# Power.net
KiCad netlist of a schematic drawn in Altium Designer
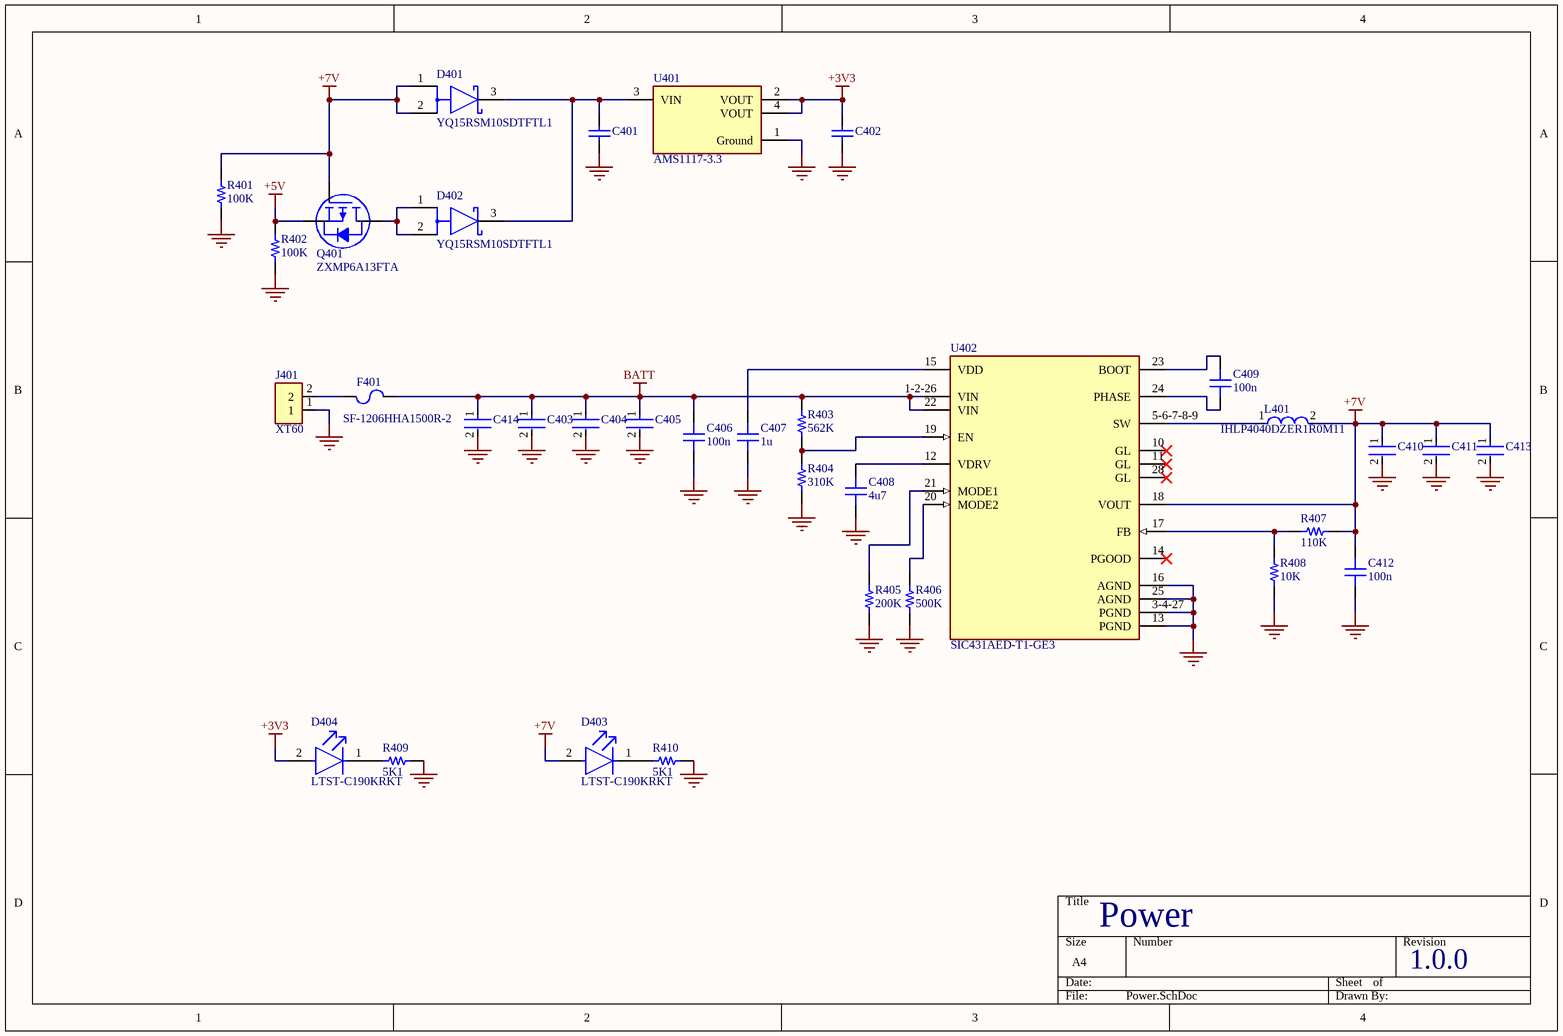
[diagram p0: Power.SchDoc]

(export (version "E")
  (design (tool "Eeschema 10.0.6"))
  (components
    (comp (ref "C401")
      (value "T529P226M010AAE200")
      (footprint "CAPC2013X100X55ML10T10")
      (fields (field (name "MANUFACTURER") "Kemet"))
      (libsource (lib "Altium Content Vault") (part "CAP"))
    )
    (comp (ref "C402")
      (value "T529P226M010AAE200")
      (footprint "CAPC2013X100X55ML10T10")
      (fields (field (name "MANUFACTURER") "Kemet"))
      (libsource (lib "Altium Content Vault") (part "CAP"))
    )
    (comp (ref "C403")
      (value "C2012X5R1V226M125AC")
      (footprint "FP-C2012-125-0_2-IPC_C")
      (description "Multilayer Ceramic Capacitors 22μF ±20% 35V X5R SMD 0805")
      (fields (field (name "TOLERANCE") "20%"))
      (libsource (lib "Altium Content Vault") (part "b4654b650e69147ec39a6b967a45e02"))
    )
    (comp (ref "C404")
      (value "C2012X5R1V226M125AC")
      (footprint "FP-C2012-125-0_2-IPC_C")
      (description "Multilayer Ceramic Capacitors 22μF ±20% 35V X5R SMD 0805")
      (fields (field (name "TOLERANCE") "20%"))
      (libsource (lib "Altium Content Vault") (part "b4654b650e69147ec39a6b967a45e02"))
    )
    (comp (ref "C405")
      (value "C2012X5R1V226M125AC")
      (footprint "FP-C2012-125-0_2-IPC_C")
      (description "Multilayer Ceramic Capacitors 22μF ±20% 35V X5R SMD 0805")
      (fields (field (name "TOLERANCE") "20%"))
      (libsource (lib "Altium Content Vault") (part "b4654b650e69147ec39a6b967a45e02"))
    )
    (comp (ref "C406")
      (value "100n")
      (footprint "CAP 0402_1005")
      (description "CAP CER 100NF 10V X7R 0402")
      (fields
        (field (name "PART NUMBER") "CL05B104KP5VPNC")
        (field (name "MANUFACTURER") "Samsung Electro-Mechanics")
      )
      (libsource (lib "Celestial Altium Library - altium_library") (part "Capacitor"))
    )
    (comp (ref "C407")
      (value "1u")
      (footprint "CAP 0402_1005")
      (description "CAP CER 100NF 10V X7R 0402")
      (fields
        (field (name "PART NUMBER") "CL05B104KP5VPNC")
        (field (name "MANUFACTURER") "Samsung Electro-Mechanics")
      )
      (libsource (lib "Celestial Altium Library - altium_library") (part "Capacitor"))
    )
    (comp (ref "C408")
      (value "4u7")
      (footprint "CAP 0603_1608")
      (description "CAP CER 4.7UF 25V X5R 0603")
      (fields
        (field (name "PART NUMBER") "CL10A475KA8NQNC")
        (field (name "MANUFACTURER") "Samsung Electro-Mechanics")
      )
      (libsource (lib "Celestial Altium Library - altium_library") (part "Capacitor"))
    )
    (comp (ref "C409")
      (value "100n")
      (footprint "CAP 0402_1005")
      (description "CAP CER 100NF 10V X7R 0402")
      (fields
        (field (name "PART NUMBER") "CL05B104KP5VPNC")
        (field (name "MANUFACTURER") "Samsung Electro-Mechanics")
      )
      (libsource (lib "Celestial Altium Library - altium_library") (part "Capacitor"))
    )
    (comp (ref "C410")
      (value "C2012X5R1V226M125AC")
      (footprint "FP-C2012-125-0_2-IPC_C")
      (description "Multilayer Ceramic Capacitors 22μF ±20% 35V X5R SMD 0805")
      (fields (field (name "TOLERANCE") "20%"))
      (libsource (lib "Altium Content Vault") (part "b4654b650e69147ec39a6b967a45e02"))
    )
    (comp (ref "C411")
      (value "C2012X5R1V226M125AC")
      (footprint "FP-C2012-125-0_2-IPC_C")
      (description "Multilayer Ceramic Capacitors 22μF ±20% 35V X5R SMD 0805")
      (fields (field (name "TOLERANCE") "20%"))
      (libsource (lib "Altium Content Vault") (part "b4654b650e69147ec39a6b967a45e02"))
    )
    (comp (ref "C412")
      (value "100n")
      (footprint "CAP 0402_1005")
      (description "CAP CER 100NF 10V X7R 0402")
      (fields
        (field (name "PART NUMBER") "CL05B104KP5VPNC")
        (field (name "MANUFACTURER") "Samsung Electro-Mechanics")
      )
      (libsource (lib "Celestial Altium Library - altium_library") (part "Capacitor"))
    )
    (comp (ref "C413")
      (value "C2012X5R1V226M125AC")
      (footprint "FP-C2012-125-0_2-IPC_C")
      (description "Multilayer Ceramic Capacitors 22μF ±20% 35V X5R SMD 0805")
      (fields (field (name "TOLERANCE") "20%"))
      (libsource (lib "Altium Content Vault") (part "b4654b650e69147ec39a6b967a45e02"))
    )
    (comp (ref "C414")
      (value "C2012X5R1V226M125AC")
      (footprint "FP-C2012-125-0_2-IPC_C")
      (description "Multilayer Ceramic Capacitors 22μF ±20% 35V X5R SMD 0805")
      (fields (field (name "TOLERANCE") "20%"))
      (libsource (lib "Altium Content Vault") (part "b4654b650e69147ec39a6b967a45e02"))
    )
    (comp (ref "D401")
      (value "YQ15RSM10SDTFTL1")
      (footprint "FP-95570-MFG")
      (description "DIODE SCHOTTKY 100V 5A TO277A")
      (libsource (lib "Altium Content Vault") (part "03725f8997c85b601c823eea96032f8"))
    )
    (comp (ref "D402")
      (value "YQ15RSM10SDTFTL1")
      (footprint "FP-95570-MFG")
      (description "DIODE SCHOTTKY 100V 5A TO277A")
      (libsource (lib "Altium Content Vault") (part "03725f8997c85b601c823eea96032f8"))
    )
    (comp (ref "D403")
      (value "LTST-C190KRKT")
      (footprint "FP-LTST-C190KRKT-MFG")
      (description "LED RED CLEAR CHIP SMD")
      (libsource (lib "Altium Content Vault") (part "8706943c75ba83719d021d2fdc84c58"))
    )
    (comp (ref "D404")
      (value "LTST-C190KRKT")
      (footprint "FP-LTST-C190KRKT-MFG")
      (description "LED RED CLEAR CHIP SMD")
      (libsource (lib "Altium Content Vault") (part "8706943c75ba83719d021d2fdc84c58"))
    )
    (comp (ref "F401")
      (value "SF-1206HHA1500R-2")
      (footprint "FUSE 1206_3216 0.6MM")
      (description "FUSE BOARD MOUNT 15A 32VDC 1206")
      (fields
        (field (name "PART NUMBER") "CC12H15A-TR")
        (field (name "MANUFACTURER") "Eaton - Electronics Division")
      )
      (libsource (lib "Celestial Altium Library - altium_library") (part "MOUNTED FUSE"))
    )
    (comp (ref "J401")
      (value "XT60")
      (footprint "AMASS_XT60PB-M")
      (description "Power connector; 65A; PIN: 2; Colour: yellow")
      (fields (field (name "MP") "XT60 YELLOW") (field (name "MF") "Pololu"))
      (libsource (lib "XT60_YELLOW") (part "XT60_YELLOW"))
    )
    (comp (ref "L401")
      (value "IHLP4040DZER1R0M11")
      (footprint "FP-IHLP-4040DZ-FP_3_175x4-MFG")
      (description "Commercial Inductors, Low DCR Series 1uH 25A 2.5mΩ 20%")
      (fields (field (name "TOLERANCE") "20%"))
      (libsource (lib "Altium Content Vault") (part "725321dda6339637d4d059423bc1c3c"))
    )
    (comp (ref "Q401")
      (value "ZXMP6A13FTA")
      (footprint "DIODES SOT-23-3")
      (description "MOSFET P-CH 60V 900MA SOT23-3")
      (fields (field (name "MANUFACTURER") "Diodes Incorporated"))
      (libsource (lib "Celestial Altium Library - altium_library") (part "DIODES MOSFET P-CH SOT-23-3"))
    )
    (comp (ref "R401")
      (value "100K")
      (footprint "RES 0402_1005")
      (description "RES SMD 5.1K OHM 5% 1/16W 0402")
      (fields (field (name "PART NUMBER") "AC0402JR-075K1L") (field (name "MANUFACTURER") "Yageo"))
      (libsource (lib "Celestial Altium Library - altium_library") (part "Resistor"))
    )
    (comp (ref "R402")
      (value "100K")
      (footprint "RES 0402_1005")
      (description "RES SMD 5.1K OHM 5% 1/16W 0402")
      (fields (field (name "PART NUMBER") "AC0402JR-075K1L") (field (name "MANUFACTURER") "Yageo"))
      (libsource (lib "Celestial Altium Library - altium_library") (part "Resistor"))
    )
    (comp (ref "R403")
      (value "562K")
      (footprint "RES 0402_1005")
      (description "RES SMD 5.1K OHM 5% 1/16W 0402")
      (fields (field (name "PART NUMBER") "AC0402JR-075K1L") (field (name "MANUFACTURER") "Yageo"))
      (libsource (lib "Celestial Altium Library - altium_library") (part "Resistor"))
    )
    (comp (ref "R404")
      (value "310K")
      (footprint "RES 0402_1005")
      (description "RES SMD 5.1K OHM 5% 1/16W 0402")
      (fields (field (name "PART NUMBER") "AC0402JR-075K1L") (field (name "MANUFACTURER") "Yageo"))
      (libsource (lib "Celestial Altium Library - altium_library") (part "Resistor"))
    )
    (comp (ref "R405")
      (value "200K")
      (footprint "RES 0402_1005")
      (description "RES SMD 5.1K OHM 5% 1/16W 0402")
      (fields (field (name "PART NUMBER") "AC0402JR-075K1L") (field (name "MANUFACTURER") "Yageo"))
      (libsource (lib "Celestial Altium Library - altium_library") (part "Resistor"))
    )
    (comp (ref "R406")
      (value "500K")
      (footprint "RES 0402_1005")
      (description "RES SMD 5.1K OHM 5% 1/16W 0402")
      (fields (field (name "PART NUMBER") "AC0402JR-075K1L") (field (name "MANUFACTURER") "Yageo"))
      (libsource (lib "Celestial Altium Library - altium_library") (part "Resistor"))
    )
    (comp (ref "R407")
      (value "110K")
      (footprint "RES 0402_1005")
      (description "RES SMD 5.1K OHM 5% 1/16W 0402")
      (fields (field (name "PART NUMBER") "AC0402JR-075K1L") (field (name "MANUFACTURER") "Yageo"))
      (libsource (lib "Celestial Altium Library - altium_library") (part "Resistor"))
    )
    (comp (ref "R408")
      (value "10K")
      (footprint "RES 0402_1005")
      (description "RES SMD 5.1K OHM 5% 1/16W 0402")
      (fields (field (name "PART NUMBER") "AC0402JR-075K1L") (field (name "MANUFACTURER") "Yageo"))
      (libsource (lib "Celestial Altium Library - altium_library") (part "Resistor"))
    )
    (comp (ref "R409")
      (value "5K1")
      (footprint "RES 0402_1005")
      (description "RES SMD 5.1K OHM 5% 1/16W 0402")
      (fields (field (name "PART NUMBER") "AC0402JR-075K1L") (field (name "MANUFACTURER") "Yageo"))
      (libsource (lib "Celestial Altium Library - altium_library") (part "Resistor"))
    )
    (comp (ref "R410")
      (value "5K1")
      (footprint "RES 0402_1005")
      (description "RES SMD 5.1K OHM 5% 1/16W 0402")
      (fields (field (name "PART NUMBER") "AC0402JR-075K1L") (field (name "MANUFACTURER") "Yageo"))
      (libsource (lib "Celestial Altium Library - altium_library") (part "Resistor"))
    )
    (comp (ref "U401")
      (value "AMS1117-3.3")
      (footprint "FP-AMS1117-IPC_C")
      (description "LDO Voltage Regulators 1A, 3.3V")
      (fields
        (field (name "OCTOPART") "https://octopart.com/ams1117-3.3-advanced+monolithic+systems-25899300")
        (field (name "MANUFACTURER") "Advanced Monolithic Systems")
      )
      (libsource (lib "Altium Content Vault") (part "8bdbb5f8e77002000e30dd2845d0354"))
    )
    (comp (ref "U402")
      (value "SIC431AED-T1-GE3")
      (footprint "FP-T22-0442-MFG")
      (description "SIC431AED-T1-GE3 IC Reg Buck Adj 24A MLP44-24")
      (libsource (lib "Altium Content Vault") (part "40dafd62ff4b33f9f37e65bbcadf93f"))
    )
  )
  (nets
    (net (code "1") (name "+3V3") (class "Default")
      (node (ref "C402") (pin "2") (pinfunction "2_2") (pintype "passive"))
      (node (ref "D404") (pin "2") (pinfunction "A_2") (pintype "passive"))
      (node (ref "U401") (pin "2") (pinfunction "VOUT_2") (pintype "passive"))
      (node (ref "U401") (pin "4") (pinfunction "VOUT_4") (pintype "passive"))
    )
    (net (code "2") (name "+5V") (class "Default")
      (node (ref "Q401") (pin "2") (pinfunction "S_2") (pintype "passive"))
      (node (ref "R402") (pin "2") (pinfunction "2_2") (pintype "passive"))
    )
    (net (code "3") (name "+7V") (class "Default")
      (node (ref "C410") (pin "1") (pinfunction "1_1") (pintype "passive"))
      (node (ref "C411") (pin "1") (pinfunction "1_1") (pintype "passive"))
      (node (ref "C412") (pin "2") (pinfunction "2_2") (pintype "passive"))
      (node (ref "C413") (pin "1") (pinfunction "1_1") (pintype "passive"))
      (node (ref "D401") (pin "1") (pinfunction "A_1") (pintype "passive"))
      (node (ref "D401") (pin "2") (pinfunction "A_2") (pintype "passive"))
      (node (ref "D403") (pin "2") (pinfunction "A_2") (pintype "passive"))
      (node (ref "L401") (pin "2") (pinfunction "2_2") (pintype "passive"))
      (node (ref "Q401") (pin "1") (pinfunction "G_1") (pintype "passive"))
      (node (ref "R401") (pin "2") (pinfunction "2_2") (pintype "passive"))
      (node (ref "R407") (pin "1") (pinfunction "1_1") (pintype "passive"))
      (node (ref "U402") (pin "18") (pinfunction "VOUT_18") (pintype "passive"))
    )
    (net (code "4") (name "BATT") (class "Default")
      (node (ref "C403") (pin "1") (pinfunction "1_1") (pintype "passive"))
      (node (ref "C404") (pin "1") (pinfunction "1_1") (pintype "passive"))
      (node (ref "C405") (pin "1") (pinfunction "1_1") (pintype "passive"))
      (node (ref "C406") (pin "2") (pinfunction "2_2") (pintype "passive"))
      (node (ref "C414") (pin "1") (pinfunction "1_1") (pintype "passive"))
      (node (ref "F401") (pin "2") (pintype "passive"))
      (node (ref "R403") (pin "1") (pinfunction "1_1") (pintype "passive"))
      (node (ref "U402") (pin "1-2-26") (pinfunction "VIN_1-2-26") (pintype "power_in"))
      (node (ref "U402") (pin "22") (pinfunction "VIN_22") (pintype "power_in"))
    )
    (net (code "5") (name "GND") (class "Default")
      (node (ref "C401") (pin "1") (pinfunction "1_1") (pintype "passive"))
      (node (ref "C402") (pin "1") (pinfunction "1_1") (pintype "passive"))
      (node (ref "C403") (pin "2") (pinfunction "2_2") (pintype "passive"))
      (node (ref "C404") (pin "2") (pinfunction "2_2") (pintype "passive"))
      (node (ref "C405") (pin "2") (pinfunction "2_2") (pintype "passive"))
      (node (ref "C406") (pin "1") (pinfunction "1_1") (pintype "passive"))
      (node (ref "C407") (pin "1") (pinfunction "1_1") (pintype "passive"))
      (node (ref "C408") (pin "1") (pinfunction "1_1") (pintype "passive"))
      (node (ref "C410") (pin "2") (pinfunction "2_2") (pintype "passive"))
      (node (ref "C411") (pin "2") (pinfunction "2_2") (pintype "passive"))
      (node (ref "C412") (pin "1") (pinfunction "1_1") (pintype "passive"))
      (node (ref "C413") (pin "2") (pinfunction "2_2") (pintype "passive"))
      (node (ref "C414") (pin "2") (pinfunction "2_2") (pintype "passive"))
      (node (ref "J401") (pin "1") (pinfunction "1_1") (pintype "passive"))
      (node (ref "R401") (pin "1") (pinfunction "1_1") (pintype "passive"))
      (node (ref "R402") (pin "1") (pinfunction "1_1") (pintype "passive"))
      (node (ref "R404") (pin "2") (pinfunction "2_2") (pintype "passive"))
      (node (ref "R405") (pin "2") (pinfunction "2_2") (pintype "passive"))
      (node (ref "R406") (pin "2") (pinfunction "2_2") (pintype "passive"))
      (node (ref "R408") (pin "2") (pinfunction "2_2") (pintype "passive"))
      (node (ref "R409") (pin "1") (pinfunction "1_1") (pintype "passive"))
      (node (ref "R410") (pin "1") (pinfunction "1_1") (pintype "passive"))
      (node (ref "U401") (pin "1") (pinfunction "Ground_1") (pintype "power_in"))
      (node (ref "U402") (pin "13") (pinfunction "PGND_13") (pintype "power_in"))
      (node (ref "U402") (pin "16") (pinfunction "AGND_16") (pintype "power_in"))
      (node (ref "U402") (pin "25") (pinfunction "AGND_25") (pintype "power_in"))
      (node (ref "U402") (pin "3-4-27") (pinfunction "PGND_3-4-27") (pintype "power_in"))
    )
    (net (code "6") (name "Net-(D401-C)") (class "Default")
      (node (ref "C401") (pin "2") (pinfunction "2_2") (pintype "passive"))
      (node (ref "D401") (pin "3") (pinfunction "C_3") (pintype "passive"))
      (node (ref "D402") (pin "3") (pinfunction "C_3") (pintype "passive"))
      (node (ref "U401") (pin "3") (pinfunction "VIN_3") (pintype "power_in"))
    )
    (net (code "7") (name "Net-(D403-C)") (class "Default")
      (node (ref "D403") (pin "1") (pinfunction "C_1") (pintype "passive"))
      (node (ref "R410") (pin "2") (pinfunction "2_2") (pintype "passive"))
    )
    (net (code "8") (name "Net-(D404-C)") (class "Default")
      (node (ref "D404") (pin "1") (pinfunction "C_1") (pintype "passive"))
      (node (ref "R409") (pin "2") (pinfunction "2_2") (pintype "passive"))
    )
    (net (code "9") (name "Net-(F401-Pad1)") (class "Default")
      (node (ref "F401") (pin "1") (pintype "passive"))
      (node (ref "J401") (pin "2") (pinfunction "2_2") (pintype "passive"))
    )
    (net (code "10") (name "Net-(Q401-D)") (class "Default")
      (node (ref "D402") (pin "1") (pinfunction "A_1") (pintype "passive"))
      (node (ref "D402") (pin "2") (pinfunction "A_2") (pintype "passive"))
      (node (ref "Q401") (pin "3") (pinfunction "D_3") (pintype "passive"))
    )
    (net (code "11") (name "Net-(U402-BOOT)") (class "Default")
      (node (ref "C409") (pin "2") (pinfunction "2_2") (pintype "passive"))
      (node (ref "U402") (pin "23") (pinfunction "BOOT_23") (pintype "passive"))
    )
    (net (code "12") (name "Net-(U402-EN)") (class "Default")
      (node (ref "R403") (pin "2") (pinfunction "2_2") (pintype "passive"))
      (node (ref "R404") (pin "1") (pinfunction "1_1") (pintype "passive"))
      (node (ref "U402") (pin "19") (pinfunction "EN_19") (pintype "input"))
    )
    (net (code "13") (name "Net-(U402-FB)") (class "Default")
      (node (ref "R407") (pin "2") (pinfunction "2_2") (pintype "passive"))
      (node (ref "R408") (pin "1") (pinfunction "1_1") (pintype "passive"))
      (node (ref "U402") (pin "17") (pinfunction "FB_17") (pintype "input"))
    )
    (net (code "14") (name "Net-(U402-MODE1)") (class "Default")
      (node (ref "R405") (pin "1") (pinfunction "1_1") (pintype "passive"))
      (node (ref "U402") (pin "21") (pinfunction "MODE1_21") (pintype "input"))
    )
    (net (code "15") (name "Net-(U402-MODE2)") (class "Default")
      (node (ref "R406") (pin "1") (pinfunction "1_1") (pintype "passive"))
      (node (ref "U402") (pin "20") (pinfunction "MODE2_20") (pintype "input"))
    )
    (net (code "16") (name "Net-(U402-PHASE)") (class "Default")
      (node (ref "C409") (pin "1") (pinfunction "1_1") (pintype "passive"))
      (node (ref "U402") (pin "24") (pinfunction "PHASE_24") (pintype "passive"))
    )
    (net (code "17") (name "Net-(U402-SW)") (class "Default")
      (node (ref "L401") (pin "1") (pinfunction "1_1") (pintype "passive"))
      (node (ref "U402") (pin "5-6-7-8-9") (pinfunction "SW_5-6-7-8-9") (pintype "passive"))
    )
    (net (code "18") (name "Net-(U402-VDD)") (class "Default")
      (node (ref "C407") (pin "2") (pinfunction "2_2") (pintype "passive"))
      (node (ref "U402") (pin "15") (pinfunction "VDD_15") (pintype "power_in"))
    )
    (net (code "19") (name "Net-(U402-VDRV)") (class "Default")
      (node (ref "C408") (pin "2") (pinfunction "2_2") (pintype "passive"))
      (node (ref "U402") (pin "12") (pinfunction "VDRV_12") (pintype "passive"))
    )
    (net (code "20") (name "unconnected-(U402-GL-Pad10)") (class "Default")
      (node (ref "U402") (pin "10") (pinfunction "GL_10") (pintype "passive+no_connect"))
    )
    (net (code "21") (name "unconnected-(U402-GL-Pad11)") (class "Default")
      (node (ref "U402") (pin "11") (pinfunction "GL_11") (pintype "passive+no_connect"))
    )
    (net (code "22") (name "unconnected-(U402-GL-Pad28)") (class "Default")
      (node (ref "U402") (pin "28") (pinfunction "GL_28") (pintype "passive+no_connect"))
    )
    (net (code "23") (name "unconnected-(U402-PGOOD-Pad14)") (class "Default")
      (node (ref "U402") (pin "14") (pinfunction "PGOOD_14") (pintype "open_collector+no_connect"))
    )
  )
)
